# PoolTable.net
KiCad netlist of a schematic drawn in EAGLE
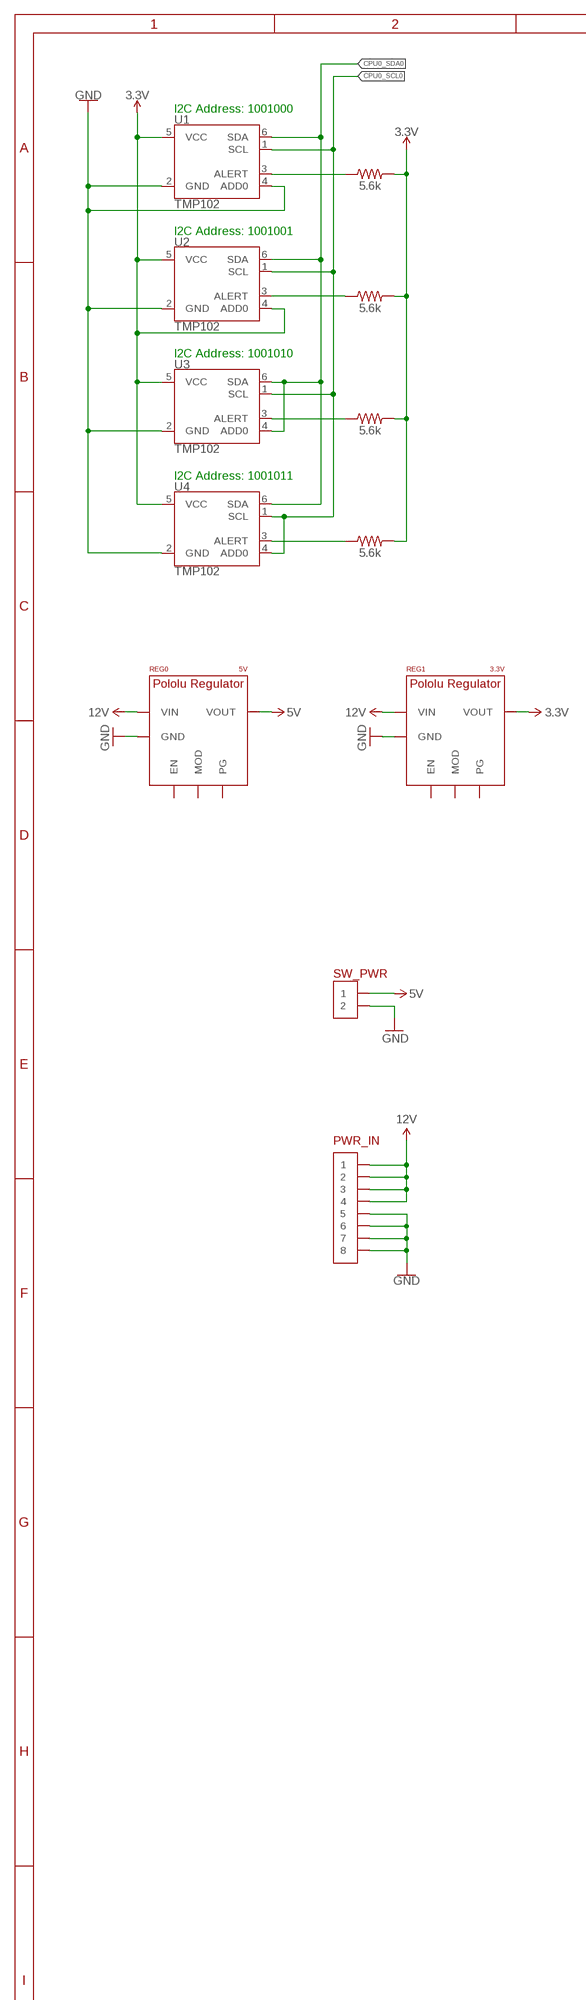
[diagram p0: schematic, sheet 1, part 1 of 2]
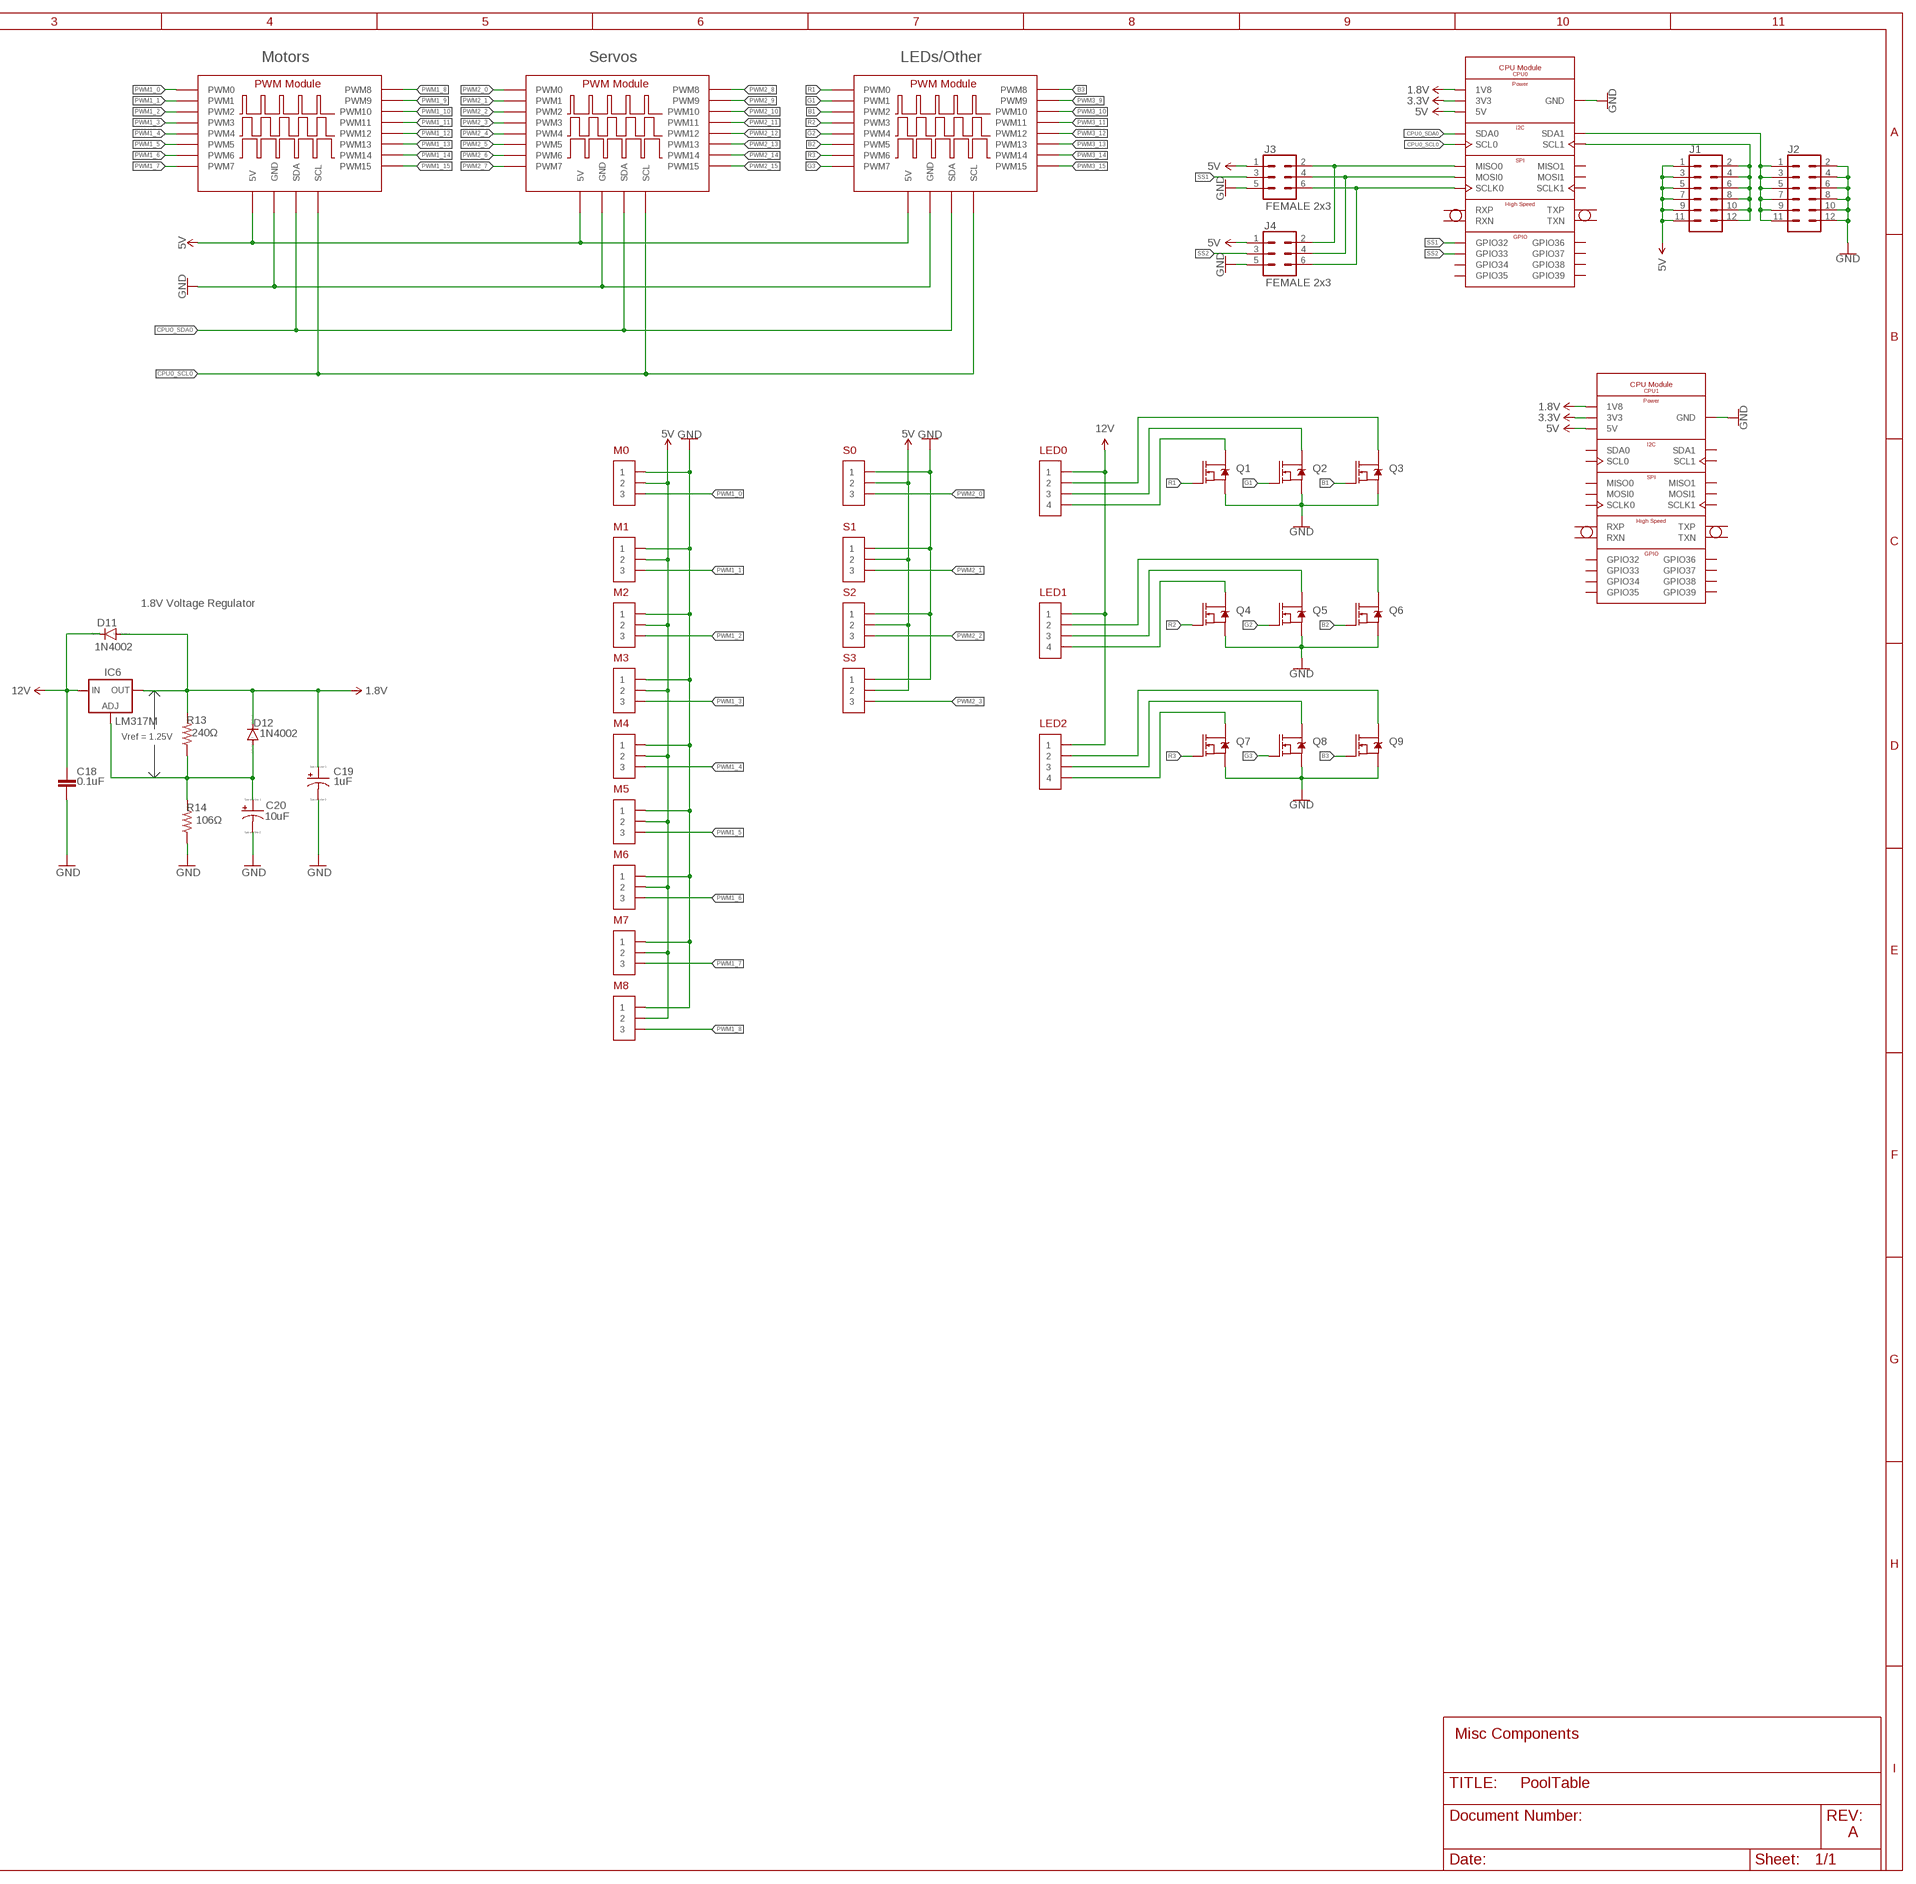
[diagram p1: schematic, sheet 1, part 2 of 2]

(export (version "E")
  (design (tool "Eeschema 10.0.6"))
  (components
    (comp (ref "C18")
      (value "0.1uF")
      (footprint "eagle-import:C075-052X106")
      (libsource (lib "eagle-import") (part "C-EU075-052X106"))
    )
    (comp (ref "C19")
      (value "1uF")
      (footprint "eagle-import:085CS_1AR")
      (libsource (lib "eagle-import") (part "CPOL-US085CS-1AR"))
    )
    (comp (ref "C20")
      (value "10uF")
      (footprint "eagle-import:085CS_1AR")
      (libsource (lib "eagle-import") (part "CPOL-US085CS-1AR"))
    )
    (comp (ref "CPU0")
      (value "CPU_MODULE")
      (footprint "eagle-import:CPU_MODULE")
      (libsource (lib "eagle-import") (part "CPU_MODULE"))
    )
    (comp (ref "CPU1")
      (value "CPU_MODULE")
      (footprint "eagle-import:CPU_MODULE")
      (libsource (lib "eagle-import") (part "CPU_MODULE"))
    )
    (comp (ref "D11")
      (value "1N4002")
      (footprint "eagle-import:DO41-10")
      (libsource (lib "eagle-import") (part "1N4004"))
    )
    (comp (ref "D12")
      (value "1N4002")
      (footprint "eagle-import:DO41-10")
      (libsource (lib "eagle-import") (part "1N4004"))
    )
    (comp (ref "IC6")
      (value "LM317MBSTT3")
      (footprint "eagle-import:SOT223")
      (fields (field (name "PARTNUMBER") "LM317M"))
      (libsource (lib "eagle-import") (part "LM317?MBSTT3"))
    )
    (comp (ref "J1")
      (value "2X6 FEMALE")
      (footprint "eagle-import:2X6")
      (libsource (lib "eagle-import") (part "CONN_06X2PTH_FEMALE"))
    )
    (comp (ref "J2")
      (value "2X6 FEMALE")
      (footprint "eagle-import:2X6")
      (libsource (lib "eagle-import") (part "CONN_06X2PTH_FEMALE"))
    )
    (comp (ref "J3")
      (value "FEMALE 2x3")
      (footprint "eagle-import:2X3")
      (libsource (lib "eagle-import") (part "CONN_03X2FEMALE"))
    )
    (comp (ref "J4")
      (value "FEMALE 2x3")
      (footprint "eagle-import:2X3")
      (libsource (lib "eagle-import") (part "CONN_03X2FEMALE"))
    )
    (comp (ref "LED0")
      (value "MOLEX-ULTRAFIT-1X04VERT")
      (footprint "eagle-import:MOLEX-ULTRAFIT-1X04V")
      (libsource (lib "eagle-import") (part "MOLEX-ULTRAFIT-1X04VERT"))
    )
    (comp (ref "LED1")
      (value "MOLEX-ULTRAFIT-1X04VERT")
      (footprint "eagle-import:MOLEX-ULTRAFIT-1X04V")
      (libsource (lib "eagle-import") (part "MOLEX-ULTRAFIT-1X04VERT"))
    )
    (comp (ref "LED2")
      (value "MOLEX-ULTRAFIT-1X04VERT")
      (footprint "eagle-import:MOLEX-ULTRAFIT-1X04V")
      (libsource (lib "eagle-import") (part "MOLEX-ULTRAFIT-1X04VERT"))
    )
    (comp (ref "M0")
      (value "MOLEX-ULTRAFIT-1X03-VERT")
      (footprint "eagle-import:MOLEX-ULTRAFIT-1X03V")
      (libsource (lib "eagle-import") (part "MOLEX-ULTRAFIT-1X03-VERT"))
    )
    (comp (ref "M1")
      (value "MOLEX-ULTRAFIT-1X03VERT")
      (footprint "eagle-import:MOLEX-ULTRAFIT-1X03V")
      (libsource (lib "eagle-import") (part "MOLEX-ULTRAFIT-1X03VERT"))
    )
    (comp (ref "M2")
      (value "MOLEX-ULTRAFIT-1X03VERT")
      (footprint "eagle-import:MOLEX-ULTRAFIT-1X03V")
      (libsource (lib "eagle-import") (part "MOLEX-ULTRAFIT-1X03VERT"))
    )
    (comp (ref "M3")
      (value "MOLEX-ULTRAFIT-1X03VERT")
      (footprint "eagle-import:MOLEX-ULTRAFIT-1X03V")
      (libsource (lib "eagle-import") (part "MOLEX-ULTRAFIT-1X03VERT"))
    )
    (comp (ref "M4")
      (value "MOLEX-ULTRAFIT-1X03VERT")
      (footprint "eagle-import:MOLEX-ULTRAFIT-1X03V")
      (libsource (lib "eagle-import") (part "MOLEX-ULTRAFIT-1X03VERT"))
    )
    (comp (ref "M5")
      (value "MOLEX-ULTRAFIT-1X03VERT")
      (footprint "eagle-import:MOLEX-ULTRAFIT-1X03V")
      (libsource (lib "eagle-import") (part "MOLEX-ULTRAFIT-1X03VERT"))
    )
    (comp (ref "M6")
      (value "MOLEX-ULTRAFIT-1X03VERT")
      (footprint "eagle-import:MOLEX-ULTRAFIT-1X03V")
      (libsource (lib "eagle-import") (part "MOLEX-ULTRAFIT-1X03VERT"))
    )
    (comp (ref "M7")
      (value "MOLEX-ULTRAFIT-1X03VERT")
      (footprint "eagle-import:MOLEX-ULTRAFIT-1X03V")
      (libsource (lib "eagle-import") (part "MOLEX-ULTRAFIT-1X03VERT"))
    )
    (comp (ref "M8")
      (value "MOLEX-ULTRAFIT-1X03-VERT")
      (footprint "eagle-import:MOLEX-ULTRAFIT-1X03V")
      (libsource (lib "eagle-import") (part "MOLEX-ULTRAFIT-1X03-VERT"))
    )
    (comp (ref "PWM0")
      (value "PWM_MODULE")
      (footprint "eagle-import:PWM_MODULE")
      (libsource (lib "eagle-import") (part "PWM_MODULE"))
    )
    (comp (ref "PWM1")
      (value "PWM_MODULE")
      (footprint "eagle-import:PWM_MODULE")
      (libsource (lib "eagle-import") (part "PWM_MODULE"))
    )
    (comp (ref "PWM2")
      (value "PWM_MODULE")
      (footprint "eagle-import:PWM_MODULE")
      (libsource (lib "eagle-import") (part "PWM_MODULE"))
    )
    (comp (ref "PWR_IN")
      (value "MOLEX-ULTRAFIT-1X08")
      (footprint "eagle-import:MOLEX-ULTRAFIT-1X08")
      (libsource (lib "eagle-import") (part "MOLEX-ULTRAFIT-1X08"))
    )
    (comp (ref "Q1")
      (value "60V/32A/35mΩ")
      (footprint "eagle-import:TO220V")
      (libsource (lib "eagle-import") (part "MOSFET-NCH-FQP30N06L"))
    )
    (comp (ref "Q2")
      (value "60V/32A/35mΩ")
      (footprint "eagle-import:TO220V")
      (libsource (lib "eagle-import") (part "MOSFET-NCH-FQP30N06L"))
    )
    (comp (ref "Q3")
      (value "60V/32A/35mΩ")
      (footprint "eagle-import:TO220V")
      (libsource (lib "eagle-import") (part "MOSFET-NCH-FQP30N06L"))
    )
    (comp (ref "Q4")
      (value "60V/32A/35mΩ")
      (footprint "eagle-import:TO220V")
      (libsource (lib "eagle-import") (part "MOSFET-NCH-FQP30N06L"))
    )
    (comp (ref "Q5")
      (value "60V/32A/35mΩ")
      (footprint "eagle-import:TO220V")
      (libsource (lib "eagle-import") (part "MOSFET-NCH-FQP30N06L"))
    )
    (comp (ref "Q6")
      (value "60V/32A/35mΩ")
      (footprint "eagle-import:TO220V")
      (libsource (lib "eagle-import") (part "MOSFET-NCH-FQP30N06L"))
    )
    (comp (ref "Q7")
      (value "60V/32A/35mΩ")
      (footprint "eagle-import:TO220V")
      (libsource (lib "eagle-import") (part "MOSFET-NCH-FQP30N06L"))
    )
    (comp (ref "Q8")
      (value "60V/32A/35mΩ")
      (footprint "eagle-import:TO220V")
      (libsource (lib "eagle-import") (part "MOSFET-NCH-FQP30N06L"))
    )
    (comp (ref "Q9")
      (value "60V/32A/35mΩ")
      (footprint "eagle-import:TO220V")
      (libsource (lib "eagle-import") (part "MOSFET-NCH-FQP30N06L"))
    )
    (comp (ref "R9")
      (value "5.6k")
      (footprint "eagle-import:0603")
      (libsource (lib "eagle-import") (part "5.6KOHM-0603-1/10W-1%"))
    )
    (comp (ref "R12")
      (value "5.6k")
      (footprint "eagle-import:0603")
      (libsource (lib "eagle-import") (part "5.6KOHM-0603-1/10W-1%"))
    )
    (comp (ref "R13")
      (value "240Ω")
      (footprint "eagle-import:M0805")
      (libsource (lib "eagle-import") (part "R-US_M0805"))
    )
    (comp (ref "R14")
      (value "106Ω")
      (footprint "eagle-import:M0805")
      (libsource (lib "eagle-import") (part "R-US_M0805"))
    )
    (comp (ref "R15")
      (value "5.6k")
      (footprint "eagle-import:0603")
      (libsource (lib "eagle-import") (part "5.6KOHM-0603-1/10W-1%"))
    )
    (comp (ref "R18")
      (value "5.6k")
      (footprint "eagle-import:0603")
      (libsource (lib "eagle-import") (part "5.6KOHM-0603-1/10W-1%"))
    )
    (comp (ref "REG0")
      (value "5V")
      (footprint "eagle-import:POLOLU-REG")
      (libsource (lib "eagle-import") (part "POLOLU-REG"))
    )
    (comp (ref "REG1")
      (value "3.3V")
      (footprint "eagle-import:POLOLU-REG")
      (libsource (lib "eagle-import") (part "POLOLU-REG"))
    )
    (comp (ref "S0")
      (value "MOLEX-ULTRAFIT-1X03VERT")
      (footprint "eagle-import:MOLEX-ULTRAFIT-1X03V")
      (libsource (lib "eagle-import") (part "MOLEX-ULTRAFIT-1X03VERT"))
    )
    (comp (ref "S1")
      (value "MOLEX-ULTRAFIT-1X03-VERT")
      (footprint "eagle-import:MOLEX-ULTRAFIT-1X03V")
      (libsource (lib "eagle-import") (part "MOLEX-ULTRAFIT-1X03-VERT"))
    )
    (comp (ref "S2")
      (value "MOLEX-ULTRAFIT-1X03VERT")
      (footprint "eagle-import:MOLEX-ULTRAFIT-1X03V")
      (libsource (lib "eagle-import") (part "MOLEX-ULTRAFIT-1X03VERT"))
    )
    (comp (ref "S3")
      (value "MOLEX-ULTRAFIT-1X03VERT")
      (footprint "eagle-import:MOLEX-ULTRAFIT-1X03V")
      (libsource (lib "eagle-import") (part "MOLEX-ULTRAFIT-1X03VERT"))
    )
    (comp (ref "SW_PWR")
      (value "MOLEX-ULTRAFIT-1X02-HORIZ")
      (footprint "eagle-import:MOLEX-ULTRAFIT-1X02H")
      (libsource (lib "eagle-import") (part "MOLEX-ULTRAFIT-1X02-HORIZ"))
    )
    (comp (ref "U1")
      (value "TMP102")
      (footprint "eagle-import:SOT563")
      (libsource (lib "eagle-import") (part "TMP102"))
    )
    (comp (ref "U2")
      (value "TMP102")
      (footprint "eagle-import:SOT563")
      (libsource (lib "eagle-import") (part "TMP102"))
    )
    (comp (ref "U3")
      (value "TMP102")
      (footprint "eagle-import:SOT563")
      (libsource (lib "eagle-import") (part "TMP102"))
    )
    (comp (ref "U4")
      (value "TMP102")
      (footprint "eagle-import:SOT563")
      (libsource (lib "eagle-import") (part "TMP102"))
    )
  )
  (nets
    (net (code "1") (name "1.8V") (class "Default")
      (node (ref "C19") (pin "+") (pinfunction "+_+") (pintype "passive"))
      (node (ref "CPU0") (pin "19") (pinfunction "1V8_19") (pintype "power_in"))
      (node (ref "CPU1") (pin "19") (pinfunction "1V8_19") (pintype "power_in"))
      (node (ref "D11") (pin "A") (pinfunction "A_A") (pintype "passive"))
      (node (ref "D12") (pin "C") (pinfunction "C_C") (pintype "passive"))
      (node (ref "IC6") (pin "4") (pinfunction "OUT_4") (pintype "passive"))
      (node (ref "R13") (pin "2") (pinfunction "2_2") (pintype "passive"))
    )
    (net (code "2") (name "3.3V") (class "Default")
      (node (ref "CPU0") (pin "20") (pinfunction "3V3_20") (pintype "power_in"))
      (node (ref "CPU1") (pin "20") (pinfunction "3V3_20") (pintype "power_in"))
      (node (ref "R12") (pin "2") (pinfunction "2_2") (pintype "passive"))
      (node (ref "R15") (pin "2") (pinfunction "2_2") (pintype "passive"))
      (node (ref "R18") (pin "2") (pinfunction "2_2") (pintype "passive"))
      (node (ref "R9") (pin "2") (pinfunction "2_2") (pintype "passive"))
      (node (ref "REG1") (pin "P$4") (pinfunction "VOUT_P$4") (pintype "power_in"))
      (node (ref "REG1") (pin "P$7") (pinfunction "VOUT_P$7") (pintype "power_in"))
      (node (ref "REG1") (pin "P$8") (pinfunction "VOUT_P$8") (pintype "power_in"))
      (node (ref "U1") (pin "5") (pinfunction "VCC_5") (pintype "bidirectional"))
      (node (ref "U2") (pin "4") (pinfunction "ADD0_4") (pintype "bidirectional"))
      (node (ref "U2") (pin "5") (pinfunction "VCC_5") (pintype "bidirectional"))
      (node (ref "U3") (pin "5") (pinfunction "VCC_5") (pintype "bidirectional"))
      (node (ref "U4") (pin "5") (pinfunction "VCC_5") (pintype "bidirectional"))
    )
    (net (code "3") (name "5V") (class "Default")
      (node (ref "CPU0") (pin "18") (pinfunction "5V_18") (pintype "power_in"))
      (node (ref "CPU1") (pin "18") (pinfunction "5V_18") (pintype "power_in"))
      (node (ref "J1") (pin "1") (pinfunction "1_1") (pintype "passive"))
      (node (ref "J1") (pin "11") (pinfunction "11_11") (pintype "passive"))
      (node (ref "J1") (pin "3") (pinfunction "3_3") (pintype "passive"))
      (node (ref "J1") (pin "5") (pinfunction "5_5") (pintype "passive"))
      (node (ref "J1") (pin "7") (pinfunction "7_7") (pintype "passive"))
      (node (ref "J1") (pin "9") (pinfunction "9_9") (pintype "passive"))
      (node (ref "J3") (pin "1") (pinfunction "1_1") (pintype "bidirectional"))
      (node (ref "J4") (pin "1") (pinfunction "1_1") (pintype "bidirectional"))
      (node (ref "M0") (pin "P$2") (pinfunction "2_P$2") (pintype "bidirectional"))
      (node (ref "M1") (pin "P$2") (pinfunction "2_P$2") (pintype "bidirectional"))
      (node (ref "M2") (pin "P$2") (pinfunction "2_P$2") (pintype "bidirectional"))
      (node (ref "M3") (pin "P$2") (pinfunction "2_P$2") (pintype "bidirectional"))
      (node (ref "M4") (pin "P$2") (pinfunction "2_P$2") (pintype "bidirectional"))
      (node (ref "M5") (pin "P$2") (pinfunction "2_P$2") (pintype "bidirectional"))
      (node (ref "M6") (pin "P$2") (pinfunction "2_P$2") (pintype "bidirectional"))
      (node (ref "M7") (pin "P$2") (pinfunction "2_P$2") (pintype "bidirectional"))
      (node (ref "M8") (pin "P$2") (pinfunction "2_P$2") (pintype "bidirectional"))
      (node (ref "PWM0") (pin "5V") (pinfunction "5V_5V") (pintype "power_in"))
      (node (ref "PWM1") (pin "5V") (pinfunction "5V_5V") (pintype "power_in"))
      (node (ref "PWM2") (pin "5V") (pinfunction "5V_5V") (pintype "power_in"))
      (node (ref "REG0") (pin "P$4") (pinfunction "VOUT_P$4") (pintype "power_in"))
      (node (ref "REG0") (pin "P$7") (pinfunction "VOUT_P$7") (pintype "power_in"))
      (node (ref "REG0") (pin "P$8") (pinfunction "VOUT_P$8") (pintype "power_in"))
      (node (ref "S0") (pin "P$2") (pinfunction "2_P$2") (pintype "bidirectional"))
      (node (ref "S1") (pin "P$2") (pinfunction "2_P$2") (pintype "bidirectional"))
      (node (ref "S2") (pin "P$2") (pinfunction "2_P$2") (pintype "bidirectional"))
      (node (ref "S3") (pin "P$2") (pinfunction "2_P$2") (pintype "bidirectional"))
      (node (ref "SW_PWR") (pin "P$1") (pinfunction "1_P$1") (pintype "bidirectional"))
    )
    (net (code "4") (name "12V") (class "Default")
      (node (ref "C18") (pin "1") (pinfunction "1_1") (pintype "passive"))
      (node (ref "D11") (pin "C") (pinfunction "C_C") (pintype "passive"))
      (node (ref "IC6") (pin "3") (pinfunction "IN_3") (pintype "input"))
      (node (ref "LED0") (pin "P$1") (pinfunction "1_P$1") (pintype "bidirectional"))
      (node (ref "LED1") (pin "P$1") (pinfunction "1_P$1") (pintype "bidirectional"))
      (node (ref "LED2") (pin "P$1") (pinfunction "1_P$1") (pintype "bidirectional"))
      (node (ref "PWR_IN") (pin "P$1") (pinfunction "1_P$1") (pintype "bidirectional"))
      (node (ref "PWR_IN") (pin "P$2") (pinfunction "2_P$2") (pintype "bidirectional"))
      (node (ref "PWR_IN") (pin "P$3") (pinfunction "3_P$3") (pintype "bidirectional"))
      (node (ref "PWR_IN") (pin "P$4") (pinfunction "4_P$4") (pintype "bidirectional"))
      (node (ref "REG0") (pin "P$1") (pinfunction "VIN_P$1") (pintype "power_in"))
      (node (ref "REG0") (pin "P$14") (pinfunction "VIN_P$14") (pintype "power_in"))
      (node (ref "REG0") (pin "P$15") (pinfunction "VIN_P$15") (pintype "power_in"))
      (node (ref "REG1") (pin "P$1") (pinfunction "VIN_P$1") (pintype "power_in"))
      (node (ref "REG1") (pin "P$14") (pinfunction "VIN_P$14") (pintype "power_in"))
      (node (ref "REG1") (pin "P$15") (pinfunction "VIN_P$15") (pintype "power_in"))
    )
    (net (code "5") (name "B1") (class "Default")
      (node (ref "PWM1") (pin "PWM2") (pinfunction "PWM2_PWM2") (pintype "output"))
      (node (ref "Q3") (pin "1") (pinfunction "G_1") (pintype "bidirectional"))
    )
    (net (code "6") (name "B2") (class "Default")
      (node (ref "PWM1") (pin "PWM5") (pinfunction "PWM5_PWM5") (pintype "output"))
      (node (ref "Q6") (pin "1") (pinfunction "G_1") (pintype "bidirectional"))
    )
    (net (code "7") (name "B3") (class "Default")
      (node (ref "PWM1") (pin "PWM8") (pinfunction "PWM8_PWM8") (pintype "output"))
      (node (ref "Q9") (pin "1") (pinfunction "G_1") (pintype "bidirectional"))
    )
    (net (code "8") (name "CPU0_SCL0") (class "Default")
      (node (ref "CPU0") (pin "15") (pinfunction "SCL0_15") (pintype "output"))
      (node (ref "PWM0") (pin "SCL") (pinfunction "SCL_SCL") (pintype "input"))
      (node (ref "PWM1") (pin "SCL") (pinfunction "SCL_SCL") (pintype "input"))
      (node (ref "PWM2") (pin "SCL") (pinfunction "SCL_SCL") (pintype "input"))
      (node (ref "U1") (pin "1") (pinfunction "SCL_1") (pintype "bidirectional"))
      (node (ref "U2") (pin "1") (pinfunction "SCL_1") (pintype "bidirectional"))
      (node (ref "U3") (pin "1") (pinfunction "SCL_1") (pintype "bidirectional"))
      (node (ref "U4") (pin "1") (pinfunction "SCL_1") (pintype "bidirectional"))
      (node (ref "U4") (pin "4") (pinfunction "ADD0_4") (pintype "bidirectional"))
    )
    (net (code "9") (name "CPU0_SDA0") (class "Default")
      (node (ref "CPU0") (pin "13") (pinfunction "SDA0_13") (pintype "bidirectional"))
      (node (ref "PWM0") (pin "SDA") (pinfunction "SDA_SDA") (pintype "input"))
      (node (ref "PWM1") (pin "SDA") (pinfunction "SDA_SDA") (pintype "input"))
      (node (ref "PWM2") (pin "SDA") (pinfunction "SDA_SDA") (pintype "input"))
      (node (ref "U1") (pin "6") (pinfunction "SDA_6") (pintype "bidirectional"))
      (node (ref "U2") (pin "6") (pinfunction "SDA_6") (pintype "bidirectional"))
      (node (ref "U3") (pin "4") (pinfunction "ADD0_4") (pintype "bidirectional"))
      (node (ref "U3") (pin "6") (pinfunction "SDA_6") (pintype "bidirectional"))
      (node (ref "U4") (pin "6") (pinfunction "SDA_6") (pintype "bidirectional"))
    )
    (net (code "10") (name "G1") (class "Default")
      (node (ref "PWM1") (pin "PWM1") (pinfunction "PWM1_PWM1") (pintype "output"))
      (node (ref "Q2") (pin "1") (pinfunction "G_1") (pintype "bidirectional"))
    )
    (net (code "11") (name "G2") (class "Default")
      (node (ref "PWM1") (pin "PWM4") (pinfunction "PWM4_PWM4") (pintype "output"))
      (node (ref "Q5") (pin "1") (pinfunction "G_1") (pintype "bidirectional"))
    )
    (net (code "12") (name "G3") (class "Default")
      (node (ref "PWM1") (pin "PWM7") (pinfunction "PWM7_PWM7") (pintype "output"))
      (node (ref "Q8") (pin "1") (pinfunction "G_1") (pintype "bidirectional"))
    )
    (net (code "13") (name "GND") (class "Default")
      (node (ref "C18") (pin "2") (pinfunction "2_2") (pintype "passive"))
      (node (ref "C19") (pin "-") (pinfunction "-_-") (pintype "passive"))
      (node (ref "C20") (pin "-") (pinfunction "-_-") (pintype "passive"))
      (node (ref "CPU0") (pin "1") (pinfunction "GND_1") (pintype "power_in"))
      (node (ref "CPU0") (pin "10") (pinfunction "GND_10") (pintype "power_in"))
      (node (ref "CPU0") (pin "11") (pinfunction "GND_11") (pintype "power_in"))
      (node (ref "CPU0") (pin "14") (pinfunction "GND_14") (pintype "power_in"))
      (node (ref "CPU0") (pin "17") (pinfunction "GND_17") (pintype "power_in"))
      (node (ref "CPU0") (pin "2") (pinfunction "GND_2") (pintype "power_in"))
      (node (ref "CPU0") (pin "21") (pinfunction "GND_21") (pintype "power_in"))
      (node (ref "CPU0") (pin "24") (pinfunction "GND_24") (pintype "power_in"))
      (node (ref "CPU0") (pin "27") (pinfunction "GND_27") (pintype "power_in"))
      (node (ref "CPU0") (pin "3") (pinfunction "GND_3") (pintype "power_in"))
      (node (ref "CPU0") (pin "30") (pinfunction "GND_30") (pintype "power_in"))
      (node (ref "CPU0") (pin "33") (pinfunction "GND_33") (pintype "power_in"))
      (node (ref "CPU0") (pin "37") (pinfunction "GND_37") (pintype "power_in"))
      (node (ref "CPU0") (pin "6") (pinfunction "GND_6") (pintype "power_in"))
      (node (ref "CPU0") (pin "7") (pinfunction "GND_7") (pintype "power_in"))
      (node (ref "CPU1") (pin "1") (pinfunction "GND_1") (pintype "power_in"))
      (node (ref "CPU1") (pin "10") (pinfunction "GND_10") (pintype "power_in"))
      (node (ref "CPU1") (pin "11") (pinfunction "GND_11") (pintype "power_in"))
      (node (ref "CPU1") (pin "14") (pinfunction "GND_14") (pintype "power_in"))
      (node (ref "CPU1") (pin "17") (pinfunction "GND_17") (pintype "power_in"))
      (node (ref "CPU1") (pin "2") (pinfunction "GND_2") (pintype "power_in"))
      (node (ref "CPU1") (pin "21") (pinfunction "GND_21") (pintype "power_in"))
      (node (ref "CPU1") (pin "24") (pinfunction "GND_24") (pintype "power_in"))
      (node (ref "CPU1") (pin "27") (pinfunction "GND_27") (pintype "power_in"))
      (node (ref "CPU1") (pin "3") (pinfunction "GND_3") (pintype "power_in"))
      (node (ref "CPU1") (pin "30") (pinfunction "GND_30") (pintype "power_in"))
      (node (ref "CPU1") (pin "33") (pinfunction "GND_33") (pintype "power_in"))
      (node (ref "CPU1") (pin "37") (pinfunction "GND_37") (pintype "power_in"))
      (node (ref "CPU1") (pin "6") (pinfunction "GND_6") (pintype "power_in"))
      (node (ref "CPU1") (pin "7") (pinfunction "GND_7") (pintype "power_in"))
      (node (ref "J2") (pin "10") (pinfunction "10_10") (pintype "passive"))
      (node (ref "J2") (pin "12") (pinfunction "12_12") (pintype "passive"))
      (node (ref "J2") (pin "2") (pinfunction "2_2") (pintype "passive"))
      (node (ref "J2") (pin "4") (pinfunction "4_4") (pintype "passive"))
      (node (ref "J2") (pin "6") (pinfunction "6_6") (pintype "passive"))
      (node (ref "J2") (pin "8") (pinfunction "8_8") (pintype "passive"))
      (node (ref "J3") (pin "5") (pinfunction "5_5") (pintype "bidirectional"))
      (node (ref "J4") (pin "5") (pinfunction "5_5") (pintype "bidirectional"))
      (node (ref "M0") (pin "P$1") (pinfunction "1_P$1") (pintype "bidirectional"))
      (node (ref "M1") (pin "P$1") (pinfunction "1_P$1") (pintype "bidirectional"))
      (node (ref "M2") (pin "P$1") (pinfunction "1_P$1") (pintype "bidirectional"))
      (node (ref "M3") (pin "P$1") (pinfunction "1_P$1") (pintype "bidirectional"))
      (node (ref "M4") (pin "P$1") (pinfunction "1_P$1") (pintype "bidirectional"))
      (node (ref "M5") (pin "P$1") (pinfunction "1_P$1") (pintype "bidirectional"))
      (node (ref "M6") (pin "P$1") (pinfunction "1_P$1") (pintype "bidirectional"))
      (node (ref "M7") (pin "P$1") (pinfunction "1_P$1") (pintype "bidirectional"))
      (node (ref "M8") (pin "P$1") (pinfunction "1_P$1") (pintype "bidirectional"))
      (node (ref "PWM0") (pin "GND") (pinfunction "GND_GND") (pintype "power_in"))
      (node (ref "PWM1") (pin "GND") (pinfunction "GND_GND") (pintype "power_in"))
      (node (ref "PWM2") (pin "GND") (pinfunction "GND_GND") (pintype "power_in"))
      (node (ref "PWR_IN") (pin "P$5") (pinfunction "5_P$5") (pintype "bidirectional"))
      (node (ref "PWR_IN") (pin "P$6") (pinfunction "6_P$6") (pintype "bidirectional"))
      (node (ref "PWR_IN") (pin "P$7") (pinfunction "7_P$7") (pintype "bidirectional"))
      (node (ref "PWR_IN") (pin "P$8") (pinfunction "8_P$8") (pintype "bidirectional"))
      (node (ref "Q1") (pin "3") (pinfunction "S_3") (pintype "bidirectional"))
      (node (ref "Q2") (pin "3") (pinfunction "S_3") (pintype "bidirectional"))
      (node (ref "Q3") (pin "3") (pinfunction "S_3") (pintype "bidirectional"))
      (node (ref "Q4") (pin "3") (pinfunction "S_3") (pintype "bidirectional"))
      (node (ref "Q5") (pin "3") (pinfunction "S_3") (pintype "bidirectional"))
      (node (ref "Q6") (pin "3") (pinfunction "S_3") (pintype "bidirectional"))
      (node (ref "Q7") (pin "3") (pinfunction "S_3") (pintype "bidirectional"))
      (node (ref "Q8") (pin "3") (pinfunction "S_3") (pintype "bidirectional"))
      (node (ref "Q9") (pin "3") (pinfunction "S_3") (pintype "bidirectional"))
      (node (ref "R14") (pin "1") (pinfunction "1_1") (pintype "passive"))
      (node (ref "REG0") (pin "P$11") (pinfunction "GND_P$11") (pintype "power_in"))
      (node (ref "REG0") (pin "P$12") (pinfunction "GND_P$12") (pintype "power_in"))
      (node (ref "REG0") (pin "P$16") (pinfunction "GND_P$16") (pintype "power_in"))
      (node (ref "REG0") (pin "P$17") (pinfunction "GND_P$17") (pintype "power_in"))
      (node (ref "REG0") (pin "P$2") (pinfunction "GND_P$2") (pintype "power_in"))
      (node (ref "REG0") (pin "P$3") (pinfunction "GND_P$3") (pintype "power_in"))
      (node (ref "REG0") (pin "P$5") (pinfunction "GND_P$5") (pintype "power_in"))
      (node (ref "REG0") (pin "P$6") (pinfunction "GND_P$6") (pintype "power_in"))
      (node (ref "REG1") (pin "P$11") (pinfunction "GND_P$11") (pintype "power_in"))
      (node (ref "REG1") (pin "P$12") (pinfunction "GND_P$12") (pintype "power_in"))
      (node (ref "REG1") (pin "P$16") (pinfunction "GND_P$16") (pintype "power_in"))
      (node (ref "REG1") (pin "P$17") (pinfunction "GND_P$17") (pintype "power_in"))
      (node (ref "REG1") (pin "P$2") (pinfunction "GND_P$2") (pintype "power_in"))
      (node (ref "REG1") (pin "P$3") (pinfunction "GND_P$3") (pintype "power_in"))
      (node (ref "REG1") (pin "P$5") (pinfunction "GND_P$5") (pintype "power_in"))
      (node (ref "REG1") (pin "P$6") (pinfunction "GND_P$6") (pintype "power_in"))
      (node (ref "S0") (pin "P$1") (pinfunction "1_P$1") (pintype "bidirectional"))
      (node (ref "S1") (pin "P$1") (pinfunction "1_P$1") (pintype "bidirectional"))
      (node (ref "S2") (pin "P$1") (pinfunction "1_P$1") (pintype "bidirectional"))
      (node (ref "S3") (pin "P$1") (pinfunction "1_P$1") (pintype "bidirectional"))
      (node (ref "SW_PWR") (pin "P$2") (pinfunction "2_P$2") (pintype "bidirectional"))
      (node (ref "U1") (pin "2") (pinfunction "GND_2") (pintype "bidirectional"))
      (node (ref "U1") (pin "4") (pinfunction "ADD0_4") (pintype "bidirectional"))
      (node (ref "U2") (pin "2") (pinfunction "GND_2") (pintype "bidirectional"))
      (node (ref "U3") (pin "2") (pinfunction "GND_2") (pintype "bidirectional"))
      (node (ref "U4") (pin "2") (pinfunction "GND_2") (pintype "bidirectional"))
    )
    (net (code "14") (name "Net-(CPU0-MISO0)") (class "Default")
      (node (ref "CPU0") (pin "39") (pinfunction "MISO0_39") (pintype "input"))
      (node (ref "J3") (pin "2") (pinfunction "2_2") (pintype "bidirectional"))
      (node (ref "J4") (pin "2") (pinfunction "2_2") (pintype "bidirectional"))
    )
    (net (code "15") (name "Net-(CPU0-MOSI0)") (class "Default")
      (node (ref "CPU0") (pin "40") (pinfunction "MOSI0_40") (pintype "output"))
      (node (ref "J3") (pin "4") (pinfunction "4_4") (pintype "bidirectional"))
      (node (ref "J4") (pin "4") (pinfunction "4_4") (pintype "bidirectional"))
    )
    (net (code "16") (name "Net-(CPU0-SCL1)") (class "Default")
      (node (ref "CPU0") (pin "12") (pinfunction "SCL1_12") (pintype "output"))
      (node (ref "J1") (pin "10") (pinfunction "10_10") (pintype "passive"))
      (node (ref "J1") (pin "12") (pinfunction "12_12") (pintype "passive"))
      (node (ref "J1") (pin "2") (pinfunction "2_2") (pintype "passive"))
      (node (ref "J1") (pin "4") (pinfunction "4_4") (pintype "passive"))
      (node (ref "J1") (pin "6") (pinfunction "6_6") (pintype "passive"))
      (node (ref "J1") (pin "8") (pinfunction "8_8") (pintype "passive"))
    )
    (net (code "17") (name "Net-(CPU0-SCLK0)") (class "Default")
      (node (ref "CPU0") (pin "38") (pinfunction "SCLK0_38") (pintype "output"))
      (node (ref "J3") (pin "6") (pinfunction "6_6") (pintype "bidirectional"))
      (node (ref "J4") (pin "6") (pinfunction "6_6") (pintype "bidirectional"))
    )
    (net (code "18") (name "Net-(CPU0-SDA1)") (class "Default")
      (node (ref "CPU0") (pin "16") (pinfunction "SDA1_16") (pintype "bidirectional"))
      (node (ref "J2") (pin "1") (pinfunction "1_1") (pintype "passive"))
      (node (ref "J2") (pin "11") (pinfunction "11_11") (pintype "passive"))
      (node (ref "J2") (pin "3") (pinfunction "3_3") (pintype "passive"))
      (node (ref "J2") (pin "5") (pinfunction "5_5") (pintype "passive"))
      (node (ref "J2") (pin "7") (pinfunction "7_7") (pintype "passive"))
      (node (ref "J2") (pin "9") (pinfunction "9_9") (pintype "passive"))
    )
    (net (code "19") (name "Net-(IC6-ADJ)") (class "Default")
      (node (ref "C20") (pin "+") (pinfunction "+_+") (pintype "passive"))
      (node (ref "D12") (pin "A") (pinfunction "A_A") (pintype "passive"))
      (node (ref "IC6") (pin "1") (pinfunction "ADJ_1") (pintype "input"))
      (node (ref "R13") (pin "1") (pinfunction "1_1") (pintype "passive"))
      (node (ref "R14") (pin "2") (pinfunction "2_2") (pintype "passive"))
    )
    (net (code "20") (name "Net-(LED0-2)") (class "Default")
      (node (ref "LED0") (pin "P$2") (pinfunction "2_P$2") (pintype "bidirectional"))
      (node (ref "Q3") (pin "2") (pinfunction "D_2") (pintype "bidirectional"))
    )
    (net (code "21") (name "Net-(LED0-3)") (class "Default")
      (node (ref "LED0") (pin "P$3") (pinfunction "3_P$3") (pintype "bidirectional"))
      (node (ref "Q2") (pin "2") (pinfunction "D_2") (pintype "bidirectional"))
    )
    (net (code "22") (name "Net-(LED0-4)") (class "Default")
      (node (ref "LED0") (pin "P$4") (pinfunction "4_P$4") (pintype "bidirectional"))
      (node (ref "Q1") (pin "2") (pinfunction "D_2") (pintype "bidirectional"))
    )
    (net (code "23") (name "Net-(LED1-2)") (class "Default")
      (node (ref "LED1") (pin "P$2") (pinfunction "2_P$2") (pintype "bidirectional"))
      (node (ref "Q6") (pin "2") (pinfunction "D_2") (pintype "bidirectional"))
    )
    (net (code "24") (name "Net-(LED1-3)") (class "Default")
      (node (ref "LED1") (pin "P$3") (pinfunction "3_P$3") (pintype "bidirectional"))
      (node (ref "Q5") (pin "2") (pinfunction "D_2") (pintype "bidirectional"))
    )
    (net (code "25") (name "Net-(LED1-4)") (class "Default")
      (node (ref "LED1") (pin "P$4") (pinfunction "4_P$4") (pintype "bidirectional"))
      (node (ref "Q4") (pin "2") (pinfunction "D_2") (pintype "bidirectional"))
    )
    (net (code "26") (name "Net-(LED2-2)") (class "Default")
      (node (ref "LED2") (pin "P$2") (pinfunction "2_P$2") (pintype "bidirectional"))
      (node (ref "Q9") (pin "2") (pinfunction "D_2") (pintype "bidirectional"))
    )
    (net (code "27") (name "Net-(LED2-3)") (class "Default")
      (node (ref "LED2") (pin "P$3") (pinfunction "3_P$3") (pintype "bidirectional"))
      (node (ref "Q8") (pin "2") (pinfunction "D_2") (pintype "bidirectional"))
    )
    (net (code "28") (name "Net-(LED2-4)") (class "Default")
      (node (ref "LED2") (pin "P$4") (pinfunction "4_P$4") (pintype "bidirectional"))
      (node (ref "Q7") (pin "2") (pinfunction "D_2") (pintype "bidirectional"))
    )
    (net (code "29") (name "Net-(U1-ALERT)") (class "Default")
      (node (ref "R9") (pin "1") (pinfunction "1_1") (pintype "passive"))
      (node (ref "U1") (pin "3") (pinfunction "ALERT_3") (pintype "bidirectional"))
    )
    (net (code "30") (name "Net-(U2-ALERT)") (class "Default")
      (node (ref "R18") (pin "1") (pinfunction "1_1") (pintype "passive"))
      (node (ref "U2") (pin "3") (pinfunction "ALERT_3") (pintype "bidirectional"))
    )
    (net (code "31") (name "Net-(U3-ALERT)") (class "Default")
      (node (ref "R12") (pin "1") (pinfunction "1_1") (pintype "passive"))
      (node (ref "U3") (pin "3") (pinfunction "ALERT_3") (pintype "bidirectional"))
    )
    (net (code "32") (name "Net-(U4-ALERT)") (class "Default")
      (node (ref "R15") (pin "1") (pinfunction "1_1") (pintype "passive"))
      (node (ref "U4") (pin "3") (pinfunction "ALERT_3") (pintype "bidirectional"))
    )
    (net (code "33") (name "PWM1_0") (class "Default")
      (node (ref "M0") (pin "P$3") (pinfunction "3_P$3") (pintype "bidirectional"))
      (node (ref "PWM0") (pin "PWM0") (pinfunction "PWM0_PWM0") (pintype "output"))
    )
    (net (code "34") (name "PWM1_1") (class "Default")
      (node (ref "M1") (pin "P$3") (pinfunction "3_P$3") (pintype "bidirectional"))
      (node (ref "PWM0") (pin "PWM1") (pinfunction "PWM1_PWM1") (pintype "output"))
    )
    (net (code "35") (name "PWM1_2") (class "Default")
      (node (ref "M2") (pin "P$3") (pinfunction "3_P$3") (pintype "bidirectional"))
      (node (ref "PWM0") (pin "PWM2") (pinfunction "PWM2_PWM2") (pintype "output"))
    )
    (net (code "36") (name "PWM1_3") (class "Default")
      (node (ref "M3") (pin "P$3") (pinfunction "3_P$3") (pintype "bidirectional"))
      (node (ref "PWM0") (pin "PWM3") (pinfunction "PWM3_PWM3") (pintype "output"))
    )
    (net (code "37") (name "PWM1_4") (class "Default")
      (node (ref "M4") (pin "P$3") (pinfunction "3_P$3") (pintype "bidirectional"))
      (node (ref "PWM0") (pin "PWM4") (pinfunction "PWM4_PWM4") (pintype "output"))
    )
    (net (code "38") (name "PWM1_5") (class "Default")
      (node (ref "M5") (pin "P$3") (pinfunction "3_P$3") (pintype "bidirectional"))
      (node (ref "PWM0") (pin "PWM5") (pinfunction "PWM5_PWM5") (pintype "output"))
    )
    (net (code "39") (name "PWM1_6") (class "Default")
      (node (ref "M6") (pin "P$3") (pinfunction "3_P$3") (pintype "bidirectional"))
      (node (ref "PWM0") (pin "PWM6") (pinfunction "PWM6_PWM6") (pintype "output"))
    )
    (net (code "40") (name "PWM1_7") (class "Default")
      (node (ref "M7") (pin "P$3") (pinfunction "3_P$3") (pintype "bidirectional"))
      (node (ref "PWM0") (pin "PWM7") (pinfunction "PWM7_PWM7") (pintype "output"))
    )
    (net (code "41") (name "PWM1_8") (class "Default")
      (node (ref "M8") (pin "P$3") (pinfunction "3_P$3") (pintype "bidirectional"))
      (node (ref "PWM0") (pin "PWM8") (pinfunction "PWM8_PWM8") (pintype "output"))
    )
    (net (code "42") (name "PWM1_9") (class "Default")
      (node (ref "PWM0") (pin "PWM9") (pinfunction "PWM9_PWM9") (pintype "output"))
    )
    (net (code "43") (name "PWM1_10") (class "Default")
      (node (ref "PWM0") (pin "PWM10") (pinfunction "PWM10_PWM10") (pintype "output"))
    )
    (net (code "44") (name "PWM1_11") (class "Default")
      (node (ref "PWM0") (pin "PWM11") (pinfunction "PWM11_PWM11") (pintype "output"))
    )
    (net (code "45") (name "PWM1_12") (class "Default")
      (node (ref "PWM0") (pin "PWM12") (pinfunction "PWM12_PWM12") (pintype "output"))
    )
    (net (code "46") (name "PWM1_13") (class "Default")
      (node (ref "PWM0") (pin "PWM13") (pinfunction "PWM13_PWM13") (pintype "output"))
    )
    (net (code "47") (name "PWM1_14") (class "Default")
      (node (ref "PWM0") (pin "PWM14") (pinfunction "PWM14_PWM14") (pintype "output"))
    )
    (net (code "48") (name "PWM1_15") (class "Default")
      (node (ref "PWM0") (pin "PWM15") (pinfunction "PWM15_PWM15") (pintype "output"))
    )
    (net (code "49") (name "PWM2_0") (class "Default")
      (node (ref "PWM2") (pin "PWM0") (pinfunction "PWM0_PWM0") (pintype "output"))
      (node (ref "S0") (pin "P$3") (pinfunction "3_P$3") (pintype "bidirectional"))
    )
    (net (code "50") (name "PWM2_1") (class "Default")
      (node (ref "PWM2") (pin "PWM1") (pinfunction "PWM1_PWM1") (pintype "output"))
      (node (ref "S1") (pin "P$3") (pinfunction "3_P$3") (pintype "bidirectional"))
    )
    (net (code "51") (name "PWM2_2") (class "Default")
      (node (ref "PWM2") (pin "PWM2") (pinfunction "PWM2_PWM2") (pintype "output"))
      (node (ref "S2") (pin "P$3") (pinfunction "3_P$3") (pintype "bidirectional"))
    )
    (net (code "52") (name "PWM2_3") (class "Default")
      (node (ref "PWM2") (pin "PWM3") (pinfunction "PWM3_PWM3") (pintype "output"))
      (node (ref "S3") (pin "P$3") (pinfunction "3_P$3") (pintype "bidirectional"))
    )
    (net (code "53") (name "PWM2_4") (class "Default")
      (node (ref "PWM2") (pin "PWM4") (pinfunction "PWM4_PWM4") (pintype "output"))
    )
    (net (code "54") (name "PWM2_5") (class "Default")
      (node (ref "PWM2") (pin "PWM5") (pinfunction "PWM5_PWM5") (pintype "output"))
    )
    (net (code "55") (name "PWM2_6") (class "Default")
      (node (ref "PWM2") (pin "PWM6") (pinfunction "PWM6_PWM6") (pintype "output"))
    )
    (net (code "56") (name "PWM2_7") (class "Default")
      (node (ref "PWM2") (pin "PWM7") (pinfunction "PWM7_PWM7") (pintype "output"))
    )
    (net (code "57") (name "PWM2_8") (class "Default")
      (node (ref "PWM2") (pin "PWM8") (pinfunction "PWM8_PWM8") (pintype "output"))
    )
    (net (code "58") (name "PWM2_9") (class "Default")
      (node (ref "PWM2") (pin "PWM9") (pinfunction "PWM9_PWM9") (pintype "output"))
    )
    (net (code "59") (name "PWM2_10") (class "Default")
      (node (ref "PWM2") (pin "PWM10") (pinfunction "PWM10_PWM10") (pintype "output"))
    )
    (net (code "60") (name "PWM2_11") (class "Default")
      (node (ref "PWM2") (pin "PWM11") (pinfunction "PWM11_PWM11") (pintype "output"))
    )
    (net (code "61") (name "PWM2_12") (class "Default")
      (node (ref "PWM2") (pin "PWM12") (pinfunction "PWM12_PWM12") (pintype "output"))
    )
    (net (code "62") (name "PWM2_13") (class "Default")
      (node (ref "PWM2") (pin "PWM13") (pinfunction "PWM13_PWM13") (pintype "output"))
    )
    (net (code "63") (name "PWM2_14") (class "Default")
      (node (ref "PWM2") (pin "PWM14") (pinfunction "PWM14_PWM14") (pintype "output"))
    )
    (net (code "64") (name "PWM2_15") (class "Default")
      (node (ref "PWM2") (pin "PWM15") (pinfunction "PWM15_PWM15") (pintype "output"))
    )
    (net (code "65") (name "PWM3_9") (class "Default")
      (node (ref "PWM1") (pin "PWM9") (pinfunction "PWM9_PWM9") (pintype "output"))
    )
    (net (code "66") (name "PWM3_10") (class "Default")
      (node (ref "PWM1") (pin "PWM10") (pinfunction "PWM10_PWM10") (pintype "output"))
    )
    (net (code "67") (name "PWM3_11") (class "Default")
      (node (ref "PWM1") (pin "PWM11") (pinfunction "PWM11_PWM11") (pintype "output"))
    )
    (net (code "68") (name "PWM3_12") (class "Default")
      (node (ref "PWM1") (pin "PWM12") (pinfunction "PWM12_PWM12") (pintype "output"))
    )
    (net (code "69") (name "PWM3_13") (class "Default")
      (node (ref "PWM1") (pin "PWM13") (pinfunction "PWM13_PWM13") (pintype "output"))
    )
    (net (code "70") (name "PWM3_14") (class "Default")
      (node (ref "PWM1") (pin "PWM14") (pinfunction "PWM14_PWM14") (pintype "output"))
    )
    (net (code "71") (name "PWM3_15") (class "Default")
      (node (ref "PWM1") (pin "PWM15") (pinfunction "PWM15_PWM15") (pintype "output"))
    )
    (net (code "72") (name "R1") (class "Default")
      (node (ref "PWM1") (pin "PWM0") (pinfunction "PWM0_PWM0") (pintype "output"))
      (node (ref "Q1") (pin "1") (pinfunction "G_1") (pintype "bidirectional"))
    )
    (net (code "73") (name "R2") (class "Default")
      (node (ref "PWM1") (pin "PWM3") (pinfunction "PWM3_PWM3") (pintype "output"))
      (node (ref "Q4") (pin "1") (pinfunction "G_1") (pintype "bidirectional"))
    )
    (net (code "74") (name "R3") (class "Default")
      (node (ref "PWM1") (pin "PWM6") (pinfunction "PWM6_PWM6") (pintype "output"))
      (node (ref "Q7") (pin "1") (pinfunction "G_1") (pintype "bidirectional"))
    )
    (net (code "75") (name "SS1") (class "Default")
      (node (ref "CPU0") (pin "32") (pinfunction "GPIO32_32") (pintype "bidirectional"))
      (node (ref "J3") (pin "3") (pinfunction "3_3") (pintype "bidirectional"))
    )
    (net (code "76") (name "SS2") (class "Default")
      (node (ref "CPU0") (pin "31") (pinfunction "GPIO33_31") (pintype "bidirectional"))
      (node (ref "J4") (pin "3") (pinfunction "3_3") (pintype "bidirectional"))
    )
    (net (code "77") (name "unconnected-(CPU0-GPIO34-Pad29)") (class "Default")
      (node (ref "CPU0") (pin "29") (pinfunction "GPIO34_29") (pintype "bidirectional"))
    )
    (net (code "78") (name "unconnected-(CPU0-GPIO35-Pad28)") (class "Default")
      (node (ref "CPU0") (pin "28") (pinfunction "GPIO35_28") (pintype "bidirectional"))
    )
    (net (code "79") (name "unconnected-(CPU0-GPIO36-Pad26)") (class "Default")
      (node (ref "CPU0") (pin "26") (pinfunction "GPIO36_26") (pintype "bidirectional"))
    )
    (net (code "80") (name "unconnected-(CPU0-GPIO37-Pad25)") (class "Default")
      (node (ref "CPU0") (pin "25") (pinfunction "GPIO37_25") (pintype "bidirectional"))
    )
    (net (code "81") (name "unconnected-(CPU0-GPIO38-Pad23)") (class "Default")
      (node (ref "CPU0") (pin "23") (pinfunction "GPIO38_23") (pintype "bidirectional"))
    )
    (net (code "82") (name "unconnected-(CPU0-GPIO39-Pad22)") (class "Default")
      (node (ref "CPU0") (pin "22") (pinfunction "GPIO39_22") (pintype "bidirectional"))
    )
    (net (code "83") (name "unconnected-(CPU0-MISO1-Pad35)") (class "Default")
      (node (ref "CPU0") (pin "35") (pinfunction "MISO1_35") (pintype "input"))
    )
    (net (code "84") (name "unconnected-(CPU0-MOSI1-Pad36)") (class "Default")
      (node (ref "CPU0") (pin "36") (pinfunction "MOSI1_36") (pintype "output"))
    )
    (net (code "85") (name "unconnected-(CPU0-RXN-Pad8)") (class "Default")
      (node (ref "CPU0") (pin "8") (pinfunction "RXN_8") (pintype "input"))
    )
    (net (code "86") (name "unconnected-(CPU0-RXP-Pad9)") (class "Default")
      (node (ref "CPU0") (pin "9") (pinfunction "RXP_9") (pintype "input"))
    )
    (net (code "87") (name "unconnected-(CPU0-SCLK1-Pad34)") (class "Default")
      (node (ref "CPU0") (pin "34") (pinfunction "SCLK1_34") (pintype "output"))
    )
    (net (code "88") (name "unconnected-(CPU0-TXN-Pad4)") (class "Default")
      (node (ref "CPU0") (pin "4") (pinfunction "TXN_4") (pintype "output"))
    )
    (net (code "89") (name "unconnected-(CPU0-TXP-Pad5)") (class "Default")
      (node (ref "CPU0") (pin "5") (pinfunction "TXP_5") (pintype "output"))
    )
    (net (code "90") (name "unconnected-(CPU1-GPIO32-Pad32)") (class "Default")
      (node (ref "CPU1") (pin "32") (pinfunction "GPIO32_32") (pintype "bidirectional"))
    )
    (net (code "91") (name "unconnected-(CPU1-GPIO33-Pad31)") (class "Default")
      (node (ref "CPU1") (pin "31") (pinfunction "GPIO33_31") (pintype "bidirectional"))
    )
    (net (code "92") (name "unconnected-(CPU1-GPIO34-Pad29)") (class "Default")
      (node (ref "CPU1") (pin "29") (pinfunction "GPIO34_29") (pintype "bidirectional"))
    )
    (net (code "93") (name "unconnected-(CPU1-GPIO35-Pad28)") (class "Default")
      (node (ref "CPU1") (pin "28") (pinfunction "GPIO35_28") (pintype "bidirectional"))
    )
    (net (code "94") (name "unconnected-(CPU1-GPIO36-Pad26)") (class "Default")
      (node (ref "CPU1") (pin "26") (pinfunction "GPIO36_26") (pintype "bidirectional"))
    )
    (net (code "95") (name "unconnected-(CPU1-GPIO37-Pad25)") (class "Default")
      (node (ref "CPU1") (pin "25") (pinfunction "GPIO37_25") (pintype "bidirectional"))
    )
    (net (code "96") (name "unconnected-(CPU1-GPIO38-Pad23)") (class "Default")
      (node (ref "CPU1") (pin "23") (pinfunction "GPIO38_23") (pintype "bidirectional"))
    )
    (net (code "97") (name "unconnected-(CPU1-GPIO39-Pad22)") (class "Default")
      (node (ref "CPU1") (pin "22") (pinfunction "GPIO39_22") (pintype "bidirectional"))
    )
    (net (code "98") (name "unconnected-(CPU1-MISO0-Pad39)") (class "Default")
      (node (ref "CPU1") (pin "39") (pinfunction "MISO0_39") (pintype "input"))
    )
    (net (code "99") (name "unconnected-(CPU1-MISO1-Pad35)") (class "Default")
      (node (ref "CPU1") (pin "35") (pinfunction "MISO1_35") (pintype "input"))
    )
    (net (code "100") (name "unconnected-(CPU1-MOSI0-Pad40)") (class "Default")
      (node (ref "CPU1") (pin "40") (pinfunction "MOSI0_40") (pintype "output"))
    )
    (net (code "101") (name "unconnected-(CPU1-MOSI1-Pad36)") (class "Default")
      (node (ref "CPU1") (pin "36") (pinfunction "MOSI1_36") (pintype "output"))
    )
    (net (code "102") (name "unconnected-(CPU1-RXN-Pad8)") (class "Default")
      (node (ref "CPU1") (pin "8") (pinfunction "RXN_8") (pintype "input"))
    )
    (net (code "103") (name "unconnected-(CPU1-RXP-Pad9)") (class "Default")
      (node (ref "CPU1") (pin "9") (pinfunction "RXP_9") (pintype "input"))
    )
    (net (code "104") (name "unconnected-(CPU1-SCL0-Pad15)") (class "Default")
      (node (ref "CPU1") (pin "15") (pinfunction "SCL0_15") (pintype "output"))
    )
    (net (code "105") (name "unconnected-(CPU1-SCL1-Pad12)") (class "Default")
      (node (ref "CPU1") (pin "12") (pinfunction "SCL1_12") (pintype "output"))
    )
    (net (code "106") (name "unconnected-(CPU1-SCLK0-Pad38)") (class "Default")
      (node (ref "CPU1") (pin "38") (pinfunction "SCLK0_38") (pintype "output"))
    )
    (net (code "107") (name "unconnected-(CPU1-SCLK1-Pad34)") (class "Default")
      (node (ref "CPU1") (pin "34") (pinfunction "SCLK1_34") (pintype "output"))
    )
    (net (code "108") (name "unconnected-(CPU1-SDA0-Pad13)") (class "Default")
      (node (ref "CPU1") (pin "13") (pinfunction "SDA0_13") (pintype "bidirectional"))
    )
    (net (code "109") (name "unconnected-(CPU1-SDA1-Pad16)") (class "Default")
      (node (ref "CPU1") (pin "16") (pinfunction "SDA1_16") (pintype "bidirectional"))
    )
    (net (code "110") (name "unconnected-(CPU1-TXN-Pad4)") (class "Default")
      (node (ref "CPU1") (pin "4") (pinfunction "TXN_4") (pintype "output"))
    )
    (net (code "111") (name "unconnected-(CPU1-TXP-Pad5)") (class "Default")
      (node (ref "CPU1") (pin "5") (pinfunction "TXP_5") (pintype "output"))
    )
    (net (code "112") (name "unconnected-(REG0-EN-PadP$13)") (class "Default")
      (node (ref "REG0") (pin "P$13") (pinfunction "EN_P$13") (pintype "bidirectional"))
    )
    (net (code "113") (name "unconnected-(REG0-MOD-PadP$10)") (class "Default")
      (node (ref "REG0") (pin "P$10") (pinfunction "MOD_P$10") (pintype "bidirectional"))
    )
    (net (code "114") (name "unconnected-(REG0-PG-PadP$9)") (class "Default")
      (node (ref "REG0") (pin "P$9") (pinfunction "PG_P$9") (pintype "bidirectional"))
    )
    (net (code "115") (name "unconnected-(REG1-EN-PadP$13)") (class "Default")
      (node (ref "REG1") (pin "P$13") (pinfunction "EN_P$13") (pintype "bidirectional"))
    )
    (net (code "116") (name "unconnected-(REG1-MOD-PadP$10)") (class "Default")
      (node (ref "REG1") (pin "P$10") (pinfunction "MOD_P$10") (pintype "bidirectional"))
    )
    (net (code "117") (name "unconnected-(REG1-PG-PadP$9)") (class "Default")
      (node (ref "REG1") (pin "P$9") (pinfunction "PG_P$9") (pintype "bidirectional"))
    )
  )
)
